# LTC2949.net
KiCad netlist of a schematic drawn in Altium Designer
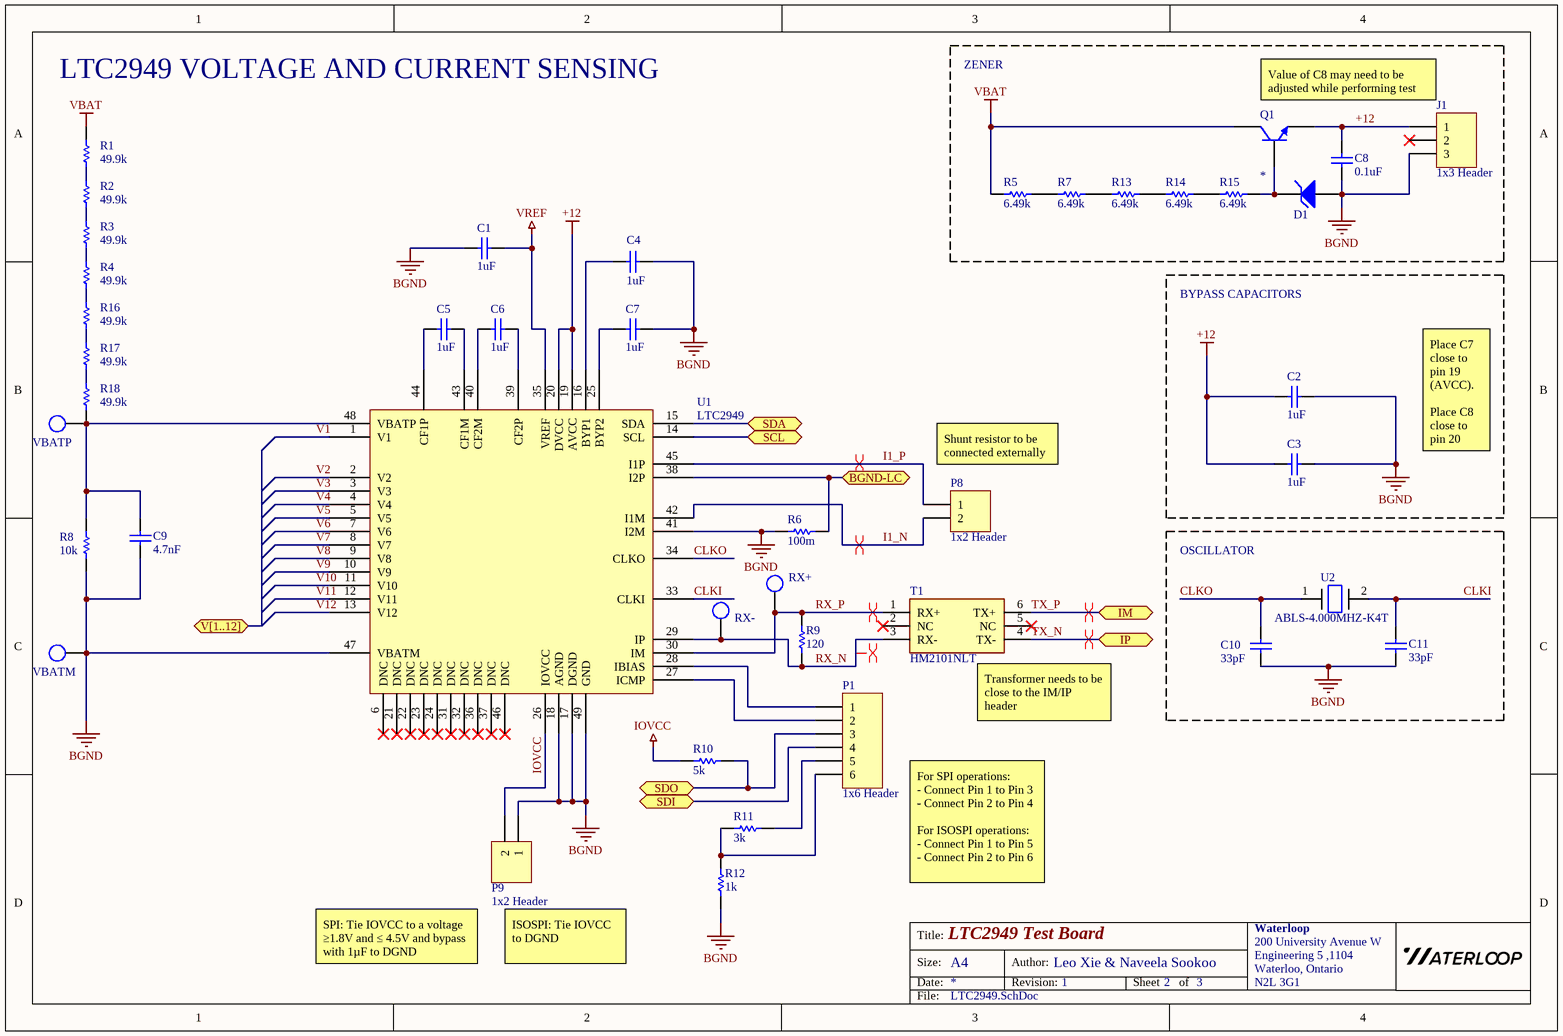
[diagram p0: LTC2949.SchDoc]

(export (version "E")
  (design (tool "Eeschema 10.0.6"))
  (components
    (comp (ref "C1")
      (value "1uF")
      (footprint "0805 - Capacitor")
      (description "Nonpolarized Capacitor")
      (fields (field (name "Comment") "Capacitor - Nonpolarized"))
      (libsource (lib "General") (part "Capacitor - Nonpolarized"))
    )
    (comp (ref "C2")
      (value "1uF")
      (footprint "0805 - Capacitor")
      (description "Nonpolarized Capacitor")
      (libsource (lib "General") (part "Capacitor - Nonpolarized"))
    )
    (comp (ref "C3")
      (value "1uF")
      (footprint "0805 - Capacitor")
      (description "Nonpolarized Capacitor")
      (libsource (lib "General") (part "Capacitor - Nonpolarized"))
    )
    (comp (ref "C4")
      (value "1uF")
      (footprint "0805 - Capacitor")
      (description "Nonpolarized Capacitor")
      (libsource (lib "General") (part "Capacitor - Nonpolarized"))
    )
    (comp (ref "C5")
      (value "1uF")
      (footprint "0805 - Capacitor")
      (description "Nonpolarized Capacitor")
      (libsource (lib "General") (part "Capacitor - Nonpolarized"))
    )
    (comp (ref "C6")
      (value "1uF")
      (footprint "0805 - Capacitor")
      (description "Nonpolarized Capacitor")
      (libsource (lib "General") (part "Capacitor - Nonpolarized"))
    )
    (comp (ref "C7")
      (value "1uF")
      (footprint "0805 - Capacitor")
      (description "Nonpolarized Capacitor")
      (libsource (lib "General") (part "Capacitor - Nonpolarized"))
    )
    (comp (ref "C8")
      (value "0.1uF")
      (footprint "0805 - Capacitor")
      (description "Nonpolarized Capacitor")
      (libsource (lib "General") (part "Capacitor - Nonpolarized"))
    )
    (comp (ref "C9")
      (value "4.7nF")
      (footprint "0805 - Capacitor")
      (description "Nonpolarized Capacitor")
      (libsource (lib "General") (part "Capacitor - Nonpolarized"))
    )
    (comp (ref "C10")
      (value "33pF")
      (footprint "0805 - Capacitor")
      (description "Nonpolarized Capacitor")
      (libsource (lib "General") (part "Capacitor - Nonpolarized"))
    )
    (comp (ref "C11")
      (value "33pF")
      (footprint "0805 - Capacitor")
      (description "Nonpolarized Capacitor")
      (libsource (lib "General") (part "Capacitor - Nonpolarized"))
    )
    (comp (ref "D1")
      (value "Zener")
      (footprint "BZD27C - ZENER DIODES")
      (description "Zener Diode")
      (libsource (lib "General") (part "Zener"))
    )
    (comp (ref "J1")
      (value "1x3 Header")
      (footprint "HDR1X3")
      (description "1x3 Pin Header")
      (libsource (lib "GeneralConnectors") (part "1x3 Header"))
    )
    (comp (ref "P1")
      (value "1x6 Header")
      (footprint "HDR1X6")
      (description "1x6 Pin Header")
      (libsource (lib "GeneralConnectors") (part "1x6 Header"))
    )
    (comp (ref "P8")
      (value "1x2 Header")
      (footprint "HDR1X2")
      (description "1x2 Pin Header")
      (libsource (lib "") (part "1x2 Header_1"))
    )
    (comp (ref "P9")
      (value "1x2 Header")
      (footprint "HDR1X2")
      (description "1x2 Pin Header")
      (libsource (lib "GeneralConnectors") (part "1x2 Header"))
    )
    (comp (ref "Q1")
      (value "NPN")
      (footprint "BJT NPN 800 V 4 A - 90 W Through Hole TO-220")
      (description "NPN Bipolar Transistor")
      (fields (field (name "ALTIUM_VALUE") "*"))
      (libsource (lib "General") (part "NPN"))
    )
    (comp (ref "R1")
      (value "49.9k")
      (footprint "1206 - Resistor")
      (description "Resistor")
      (libsource (lib "General") (part "Resistor"))
    )
    (comp (ref "R2")
      (value "49.9k")
      (footprint "1206 - Resistor")
      (description "Resistor")
      (libsource (lib "General") (part "Resistor"))
    )
    (comp (ref "R3")
      (value "49.9k")
      (footprint "1206 - Resistor")
      (description "Resistor")
      (libsource (lib "General") (part "Resistor"))
    )
    (comp (ref "R4")
      (value "49.9k")
      (footprint "1206 - Resistor")
      (description "Resistor")
      (libsource (lib "General") (part "Resistor"))
    )
    (comp (ref "R5")
      (value "6.49k")
      (footprint "0603 - Resistor")
      (description "Resistor")
      (libsource (lib "General") (part "Resistor"))
    )
    (comp (ref "R6")
      (value "100m")
      (footprint "0603 - Resistor")
      (description "Resistor")
      (libsource (lib "General") (part "Resistor"))
    )
    (comp (ref "R7")
      (value "6.49k")
      (footprint "0603 - Resistor")
      (description "Resistor")
      (libsource (lib "General") (part "Resistor"))
    )
    (comp (ref "R8")
      (value "10k")
      (footprint "0603 - Resistor")
      (description "Resistor")
      (libsource (lib "General") (part "Resistor"))
    )
    (comp (ref "R9")
      (value "120")
      (footprint "0603 - Resistor")
      (description "Resistor")
      (libsource (lib "General") (part "Resistor"))
    )
    (comp (ref "R10")
      (value "5k")
      (footprint "0603 - Resistor")
      (description "Resistor")
      (libsource (lib "General") (part "Resistor"))
    )
    (comp (ref "R11")
      (value "3k")
      (footprint "0603 - Resistor")
      (description "Resistor")
      (libsource (lib "General") (part "Resistor"))
    )
    (comp (ref "R12")
      (value "1k")
      (footprint "0603 - Resistor")
      (description "Resistor")
      (libsource (lib "General") (part "Resistor"))
    )
    (comp (ref "R13")
      (value "6.49k")
      (footprint "0603 - Resistor")
      (description "Resistor")
      (libsource (lib "General") (part "Resistor"))
    )
    (comp (ref "R14")
      (value "6.49k")
      (footprint "0603 - Resistor")
      (description "Resistor")
      (libsource (lib "General") (part "Resistor"))
    )
    (comp (ref "R15")
      (value "6.49k")
      (footprint "0603 - Resistor")
      (description "Resistor")
      (libsource (lib "General") (part "Resistor"))
    )
    (comp (ref "R16")
      (value "49.9k")
      (footprint "1206 - Resistor")
      (description "Resistor")
      (libsource (lib "General") (part "Resistor"))
    )
    (comp (ref "R17")
      (value "49.9k")
      (footprint "1206 - Resistor")
      (description "Resistor")
      (libsource (lib "General") (part "Resistor"))
    )
    (comp (ref "R18")
      (value "49.9k")
      (footprint "1206 - Resistor")
      (description "Resistor")
      (libsource (lib "General") (part "Resistor"))
    )
    (comp (ref "RX+")
      (value "Test Point")
      (footprint "Test Point - 5002")
      (libsource (lib "General") (part "Test Point"))
    )
    (comp (ref "RX-")
      (value "Test Point")
      (footprint "Test Point - 5002")
      (libsource (lib "General") (part "Test Point"))
    )
    (comp (ref "T1")
      (value "HM2101NLT")
      (footprint "HM2101NLT")
      (description "Pulse Transformer 1:1 Surface Mount 150µH, 450µH")
      (libsource (lib "GeneralComponents") (part "HM2101NLT"))
    )
    (comp (ref "U1")
      (value "LTC2949")
      (footprint "LTC2949")
      (fields
        (field (name "MANUFACTURER") "Analog Devices")
        (field (name "MANUFACTURER PART NUMBER") "LTC2949ILXE#3ZZPBF")
      )
      (libsource (lib "BMS") (part "LTC2949"))
    )
    (comp (ref "U2")
      (value "ABLS-4.000MHZ-K4T")
      (footprint "ABLS_4MHZ-K4T")
      (description "Crystal Oscillator 4MHz 18pF")
      (libsource (lib "BMS") (part "ABLS-4.000MHZ-K4T"))
    )
    (comp (ref "VBATM")
      (value "Test Point")
      (footprint "Test Point - 5002")
      (libsource (lib "General") (part "Test Point"))
    )
    (comp (ref "VBATP")
      (value "Test Point")
      (footprint "Test Point - 5002")
      (libsource (lib "General") (part "Test Point"))
    )
  )
  (nets
    (net (code "1") (name "+12") (class "Default")
      (node (ref "C2") (pin "1") (pinfunction "1_1") (pintype "passive"))
      (node (ref "C3") (pin "1") (pinfunction "1_1") (pintype "passive"))
      (node (ref "C8") (pin "1") (pinfunction "1_1") (pintype "passive"))
      (node (ref "J1") (pin "1") (pinfunction "1_1") (pintype "passive"))
      (node (ref "Q1") (pin "3") (pinfunction "E_3") (pintype "passive"))
      (node (ref "U1") (pin "19") (pinfunction "AVCC_19") (pintype "power_in"))
      (node (ref "U1") (pin "20") (pinfunction "DVCC_20") (pintype "power_in"))
    )
    (net (code "3") (name "/BGND-LC") (class "Default")
      (node (ref "R6") (pin "2") (pinfunction "2_2") (pintype "passive"))
      (node (ref "U1") (pin "38") (pinfunction "I2P_38") (pintype "passive"))
    )
    (net (code "4") (name "/CLKI") (class "Default")
      (node (ref "C11") (pin "2") (pinfunction "2_2") (pintype "passive"))
      (node (ref "U1") (pin "33") (pinfunction "CLKI_33") (pintype "passive"))
      (node (ref "U2") (pin "2") (pinfunction "2_2") (pintype "passive"))
    )
    (net (code "5") (name "/CLKO") (class "Default")
      (node (ref "C10") (pin "2") (pinfunction "2_2") (pintype "passive"))
      (node (ref "U1") (pin "34") (pinfunction "CLKO_34") (pintype "passive"))
      (node (ref "U2") (pin "1") (pinfunction "1_1") (pintype "passive"))
    )
    (net (code "6") (name "/I1_N") (class "Default")
      (node (ref "P8") (pin "2") (pinfunction "2_2") (pintype "passive"))
      (node (ref "U1") (pin "42") (pinfunction "I1M_42") (pintype "passive"))
    )
    (net (code "7") (name "/I1_P") (class "Default")
      (node (ref "P8") (pin "1") (pinfunction "1_1") (pintype "passive"))
      (node (ref "U1") (pin "45") (pinfunction "I1P_45") (pintype "passive"))
    )
    (net (code "8") (name "/RX_N") (class "Default")
      (node (ref "R9") (pin "1") (pinfunction "1_1") (pintype "passive"))
      (node (ref "RX-") (pin "1") (pinfunction "0_1") (pintype "passive"))
      (node (ref "T1") (pin "3") (pinfunction "RX-_3") (pintype "passive"))
      (node (ref "U1") (pin "29") (pinfunction "IP_29") (pintype "passive"))
    )
    (net (code "9") (name "/RX_P") (class "Default")
      (node (ref "R9") (pin "2") (pinfunction "2_2") (pintype "passive"))
      (node (ref "RX+") (pin "1") (pinfunction "0_1") (pintype "passive"))
      (node (ref "T1") (pin "1") (pinfunction "RX+_1") (pintype "passive"))
      (node (ref "U1") (pin "30") (pinfunction "IM_30") (pintype "passive"))
    )
    (net (code "10") (name "/SCL") (class "Default")
      (node (ref "U1") (pin "14") (pinfunction "SCL_14") (pintype "passive"))
    )
    (net (code "11") (name "/SDA") (class "Default")
      (node (ref "U1") (pin "15") (pinfunction "SDA_15") (pintype "passive"))
    )
    (net (code "12") (name "/SDI") (class "Default")
      (node (ref "P1") (pin "4") (pinfunction "4_4") (pintype "passive"))
    )
    (net (code "13") (name "/SDO") (class "Default")
      (node (ref "P1") (pin "3") (pinfunction "3_3") (pintype "passive"))
      (node (ref "R10") (pin "2") (pinfunction "2_2") (pintype "passive"))
    )
    (net (code "14") (name "/TX_N") (class "Default")
      (node (ref "T1") (pin "4") (pinfunction "TX-_4") (pintype "passive"))
    )
    (net (code "15") (name "/TX_P") (class "Default")
      (node (ref "T1") (pin "6") (pinfunction "TX+_6") (pintype "passive"))
    )
    (net (code "16") (name "/V1") (class "Default")
      (node (ref "U1") (pin "1") (pinfunction "V1_1") (pintype "passive"))
    )
    (net (code "17") (name "/V2") (class "Default")
      (node (ref "U1") (pin "2") (pinfunction "V2_2") (pintype "passive"))
    )
    (net (code "18") (name "/V3") (class "Default")
      (node (ref "U1") (pin "3") (pinfunction "V3_3") (pintype "passive"))
    )
    (net (code "19") (name "/V4") (class "Default")
      (node (ref "U1") (pin "4") (pinfunction "V4_4") (pintype "passive"))
    )
    (net (code "20") (name "/V5") (class "Default")
      (node (ref "U1") (pin "5") (pinfunction "V5_5") (pintype "passive"))
    )
    (net (code "21") (name "/V6") (class "Default")
      (node (ref "U1") (pin "7") (pinfunction "V6_7") (pintype "passive"))
    )
    (net (code "22") (name "/V7") (class "Default")
      (node (ref "U1") (pin "8") (pinfunction "V7_8") (pintype "passive"))
    )
    (net (code "23") (name "/V8") (class "Default")
      (node (ref "U1") (pin "9") (pinfunction "V8_9") (pintype "passive"))
    )
    (net (code "24") (name "/V9") (class "Default")
      (node (ref "U1") (pin "10") (pinfunction "V9_10") (pintype "passive"))
    )
    (net (code "25") (name "/V10") (class "Default")
      (node (ref "U1") (pin "11") (pinfunction "V10_11") (pintype "passive"))
    )
    (net (code "26") (name "/V11") (class "Default")
      (node (ref "U1") (pin "12") (pinfunction "V11_12") (pintype "passive"))
    )
    (net (code "27") (name "/V12") (class "Default")
      (node (ref "U1") (pin "13") (pinfunction "V12_13") (pintype "passive"))
    )
    (net (code "29") (name "BGND") (class "Default")
      (node (ref "C1") (pin "1") (pinfunction "1_1") (pintype "passive"))
      (node (ref "C10") (pin "1") (pinfunction "1_1") (pintype "passive"))
      (node (ref "C11") (pin "1") (pinfunction "1_1") (pintype "passive"))
      (node (ref "C2") (pin "2") (pinfunction "2_2") (pintype "passive"))
      (node (ref "C3") (pin "2") (pinfunction "2_2") (pintype "passive"))
      (node (ref "C4") (pin "2") (pinfunction "2_2") (pintype "passive"))
      (node (ref "C7") (pin "2") (pinfunction "2_2") (pintype "passive"))
      (node (ref "C8") (pin "2") (pinfunction "2_2") (pintype "passive"))
      (node (ref "C9") (pin "1") (pinfunction "1_1") (pintype "passive"))
      (node (ref "D1") (pin "1") (pinfunction "A_1") (pintype "passive"))
      (node (ref "J1") (pin "3") (pinfunction "3_3") (pintype "passive"))
      (node (ref "P9") (pin "1") (pinfunction "1_1") (pintype "passive"))
      (node (ref "R12") (pin "2") (pinfunction "2_2") (pintype "passive"))
      (node (ref "R6") (pin "1") (pinfunction "1_1") (pintype "passive"))
      (node (ref "R8") (pin "1") (pinfunction "1_1") (pintype "passive"))
      (node (ref "U1") (pin "17") (pinfunction "DGND_17") (pintype "power_in"))
      (node (ref "U1") (pin "18") (pinfunction "AGND_18") (pintype "power_in"))
      (node (ref "U1") (pin "41") (pinfunction "I2M_41") (pintype "passive"))
      (node (ref "U1") (pin "47") (pinfunction "VBATM_47") (pintype "passive"))
      (node (ref "U1") (pin "49") (pinfunction "GND_49") (pintype "power_in"))
      (node (ref "VBATM") (pin "1") (pinfunction "0_1") (pintype "passive"))
    )
    (net (code "30") (name "IOVCC") (class "Default")
      (node (ref "P9") (pin "2") (pinfunction "2_2") (pintype "passive"))
      (node (ref "R10") (pin "1") (pinfunction "1_1") (pintype "passive"))
      (node (ref "U1") (pin "26") (pinfunction "IOVCC_26") (pintype "power_in"))
    )
    (net (code "31") (name "Net-(D1-K)") (class "Default")
      (node (ref "D1") (pin "2") (pinfunction "K_2") (pintype "passive"))
      (node (ref "Q1") (pin "2") (pinfunction "B_2") (pintype "passive"))
      (node (ref "R15") (pin "1") (pinfunction "1_1") (pintype "passive"))
    )
    (net (code "32") (name "Net-(P1-Pad5)") (class "Default")
      (node (ref "P1") (pin "5") (pinfunction "5_5") (pintype "passive"))
      (node (ref "R11") (pin "2") (pinfunction "2_2") (pintype "passive"))
    )
    (net (code "33") (name "Net-(P1-Pad6)") (class "Default")
      (node (ref "P1") (pin "6") (pinfunction "6_6") (pintype "passive"))
      (node (ref "R11") (pin "1") (pinfunction "1_1") (pintype "passive"))
      (node (ref "R12") (pin "1") (pinfunction "1_1") (pintype "passive"))
    )
    (net (code "34") (name "Net-(R1-Pad1)") (class "Default")
      (node (ref "R1") (pin "1") (pinfunction "1_1") (pintype "passive"))
      (node (ref "R2") (pin "2") (pinfunction "2_2") (pintype "passive"))
    )
    (net (code "35") (name "Net-(R2-Pad1)") (class "Default")
      (node (ref "R2") (pin "1") (pinfunction "1_1") (pintype "passive"))
      (node (ref "R3") (pin "2") (pinfunction "2_2") (pintype "passive"))
    )
    (net (code "36") (name "Net-(R3-Pad1)") (class "Default")
      (node (ref "R3") (pin "1") (pinfunction "1_1") (pintype "passive"))
      (node (ref "R4") (pin "2") (pinfunction "2_2") (pintype "passive"))
    )
    (net (code "37") (name "Net-(R5-Pad1)") (class "Default")
      (node (ref "R5") (pin "1") (pinfunction "1_1") (pintype "passive"))
      (node (ref "R7") (pin "2") (pinfunction "2_2") (pintype "passive"))
    )
    (net (code "38") (name "Net-(R13-Pad1)") (class "Default")
      (node (ref "R13") (pin "1") (pinfunction "1_1") (pintype "passive"))
      (node (ref "R14") (pin "2") (pinfunction "2_2") (pintype "passive"))
    )
    (net (code "39") (name "Net-(R13-Pad2)") (class "Default")
      (node (ref "R13") (pin "2") (pinfunction "2_2") (pintype "passive"))
      (node (ref "R7") (pin "1") (pinfunction "1_1") (pintype "passive"))
    )
    (net (code "40") (name "Net-(R14-Pad1)") (class "Default")
      (node (ref "R14") (pin "1") (pinfunction "1_1") (pintype "passive"))
      (node (ref "R15") (pin "2") (pinfunction "2_2") (pintype "passive"))
    )
    (net (code "41") (name "Net-(R16-Pad1)") (class "Default")
      (node (ref "R16") (pin "1") (pinfunction "1_1") (pintype "passive"))
      (node (ref "R17") (pin "2") (pinfunction "2_2") (pintype "passive"))
    )
    (net (code "42") (name "Net-(R16-Pad2)") (class "Default")
      (node (ref "R16") (pin "2") (pinfunction "2_2") (pintype "passive"))
      (node (ref "R4") (pin "1") (pinfunction "1_1") (pintype "passive"))
    )
    (net (code "43") (name "Net-(R17-Pad1)") (class "Default")
      (node (ref "R17") (pin "1") (pinfunction "1_1") (pintype "passive"))
      (node (ref "R18") (pin "2") (pinfunction "2_2") (pintype "passive"))
    )
    (net (code "44") (name "Net-(U1-BYP1)") (class "Default")
      (node (ref "C4") (pin "1") (pinfunction "1_1") (pintype "passive"))
      (node (ref "U1") (pin "16") (pinfunction "BYP1_16") (pintype "power_in"))
    )
    (net (code "45") (name "Net-(U1-BYP2)") (class "Default")
      (node (ref "C7") (pin "1") (pinfunction "1_1") (pintype "passive"))
      (node (ref "U1") (pin "25") (pinfunction "BYP2_25") (pintype "power_in"))
    )
    (net (code "46") (name "Net-(U1-CF1M)") (class "Default")
      (node (ref "C5") (pin "2") (pinfunction "2_2") (pintype "passive"))
      (node (ref "U1") (pin "43") (pinfunction "CF1M_43") (pintype "passive"))
    )
    (net (code "47") (name "Net-(U1-CF1P)") (class "Default")
      (node (ref "C5") (pin "1") (pinfunction "1_1") (pintype "passive"))
      (node (ref "U1") (pin "44") (pinfunction "CF1P_44") (pintype "passive"))
    )
    (net (code "48") (name "Net-(U1-CF2M)") (class "Default")
      (node (ref "C6") (pin "1") (pinfunction "1_1") (pintype "passive"))
      (node (ref "U1") (pin "40") (pinfunction "CF2M_40") (pintype "passive"))
    )
    (net (code "49") (name "Net-(U1-CF2P)") (class "Default")
      (node (ref "C6") (pin "2") (pinfunction "2_2") (pintype "passive"))
      (node (ref "U1") (pin "39") (pinfunction "CF2P_39") (pintype "passive"))
    )
    (net (code "50") (name "Net-(U1-IBIAS)") (class "Default")
      (node (ref "P1") (pin "1") (pinfunction "1_1") (pintype "passive"))
      (node (ref "U1") (pin "28") (pinfunction "IBIAS_28") (pintype "passive"))
    )
    (net (code "51") (name "Net-(U1-ICMP)") (class "Default")
      (node (ref "P1") (pin "2") (pinfunction "2_2") (pintype "passive"))
      (node (ref "U1") (pin "27") (pinfunction "ICMP_27") (pintype "passive"))
    )
    (net (code "52") (name "Net-(U1-VBATP)") (class "Default")
      (node (ref "C9") (pin "2") (pinfunction "2_2") (pintype "passive"))
      (node (ref "R18") (pin "1") (pinfunction "1_1") (pintype "passive"))
      (node (ref "R8") (pin "2") (pinfunction "2_2") (pintype "passive"))
      (node (ref "U1") (pin "48") (pinfunction "VBATP_48") (pintype "passive"))
      (node (ref "VBATP") (pin "1") (pinfunction "0_1") (pintype "passive"))
    )
    (net (code "53") (name "VBAT") (class "Default")
      (node (ref "Q1") (pin "1") (pinfunction "C_1") (pintype "passive"))
      (node (ref "R1") (pin "2") (pinfunction "2_2") (pintype "passive"))
      (node (ref "R5") (pin "2") (pinfunction "2_2") (pintype "passive"))
    )
    (net (code "54") (name "VREF") (class "Default")
      (node (ref "C1") (pin "2") (pinfunction "2_2") (pintype "passive"))
      (node (ref "U1") (pin "35") (pinfunction "VREF_35") (pintype "power_in"))
    )
    (net (code "55") (name "unconnected-(J1-Pad2)") (class "Default")
      (node (ref "J1") (pin "2") (pinfunction "2_2") (pintype "passive+no_connect"))
    )
    (net (code "56") (name "unconnected-(T1-NC-Pad2)") (class "Default")
      (node (ref "T1") (pin "2") (pinfunction "NC_2") (pintype "passive+no_connect"))
    )
    (net (code "57") (name "unconnected-(T1-NC-Pad5)") (class "Default")
      (node (ref "T1") (pin "5") (pinfunction "NC_5") (pintype "passive+no_connect"))
    )
    (net (code "58") (name "unconnected-(U1-DNC-Pad6)") (class "Default")
      (node (ref "U1") (pin "6") (pinfunction "DNC_6") (pintype "passive+no_connect"))
    )
    (net (code "59") (name "unconnected-(U1-DNC-Pad21)") (class "Default")
      (node (ref "U1") (pin "21") (pinfunction "DNC_21") (pintype "passive+no_connect"))
    )
    (net (code "60") (name "unconnected-(U1-DNC-Pad22)") (class "Default")
      (node (ref "U1") (pin "22") (pinfunction "DNC_22") (pintype "passive+no_connect"))
    )
    (net (code "61") (name "unconnected-(U1-DNC-Pad23)") (class "Default")
      (node (ref "U1") (pin "23") (pinfunction "DNC_23") (pintype "passive+no_connect"))
    )
    (net (code "62") (name "unconnected-(U1-DNC-Pad24)") (class "Default")
      (node (ref "U1") (pin "24") (pinfunction "DNC_24") (pintype "passive+no_connect"))
    )
    (net (code "63") (name "unconnected-(U1-DNC-Pad31)") (class "Default")
      (node (ref "U1") (pin "31") (pinfunction "DNC_31") (pintype "passive+no_connect"))
    )
    (net (code "64") (name "unconnected-(U1-DNC-Pad32)") (class "Default")
      (node (ref "U1") (pin "32") (pinfunction "DNC_32") (pintype "passive+no_connect"))
    )
    (net (code "65") (name "unconnected-(U1-DNC-Pad36)") (class "Default")
      (node (ref "U1") (pin "36") (pinfunction "DNC_36") (pintype "passive+no_connect"))
    )
    (net (code "66") (name "unconnected-(U1-DNC-Pad37)") (class "Default")
      (node (ref "U1") (pin "37") (pinfunction "DNC_37") (pintype "passive+no_connect"))
    )
    (net (code "67") (name "unconnected-(U1-DNC-Pad46)") (class "Default")
      (node (ref "U1") (pin "46") (pinfunction "DNC_46") (pintype "passive+no_connect"))
    )
  )
)
